# Control.net
KiCad netlist of a schematic drawn in Altium Designer
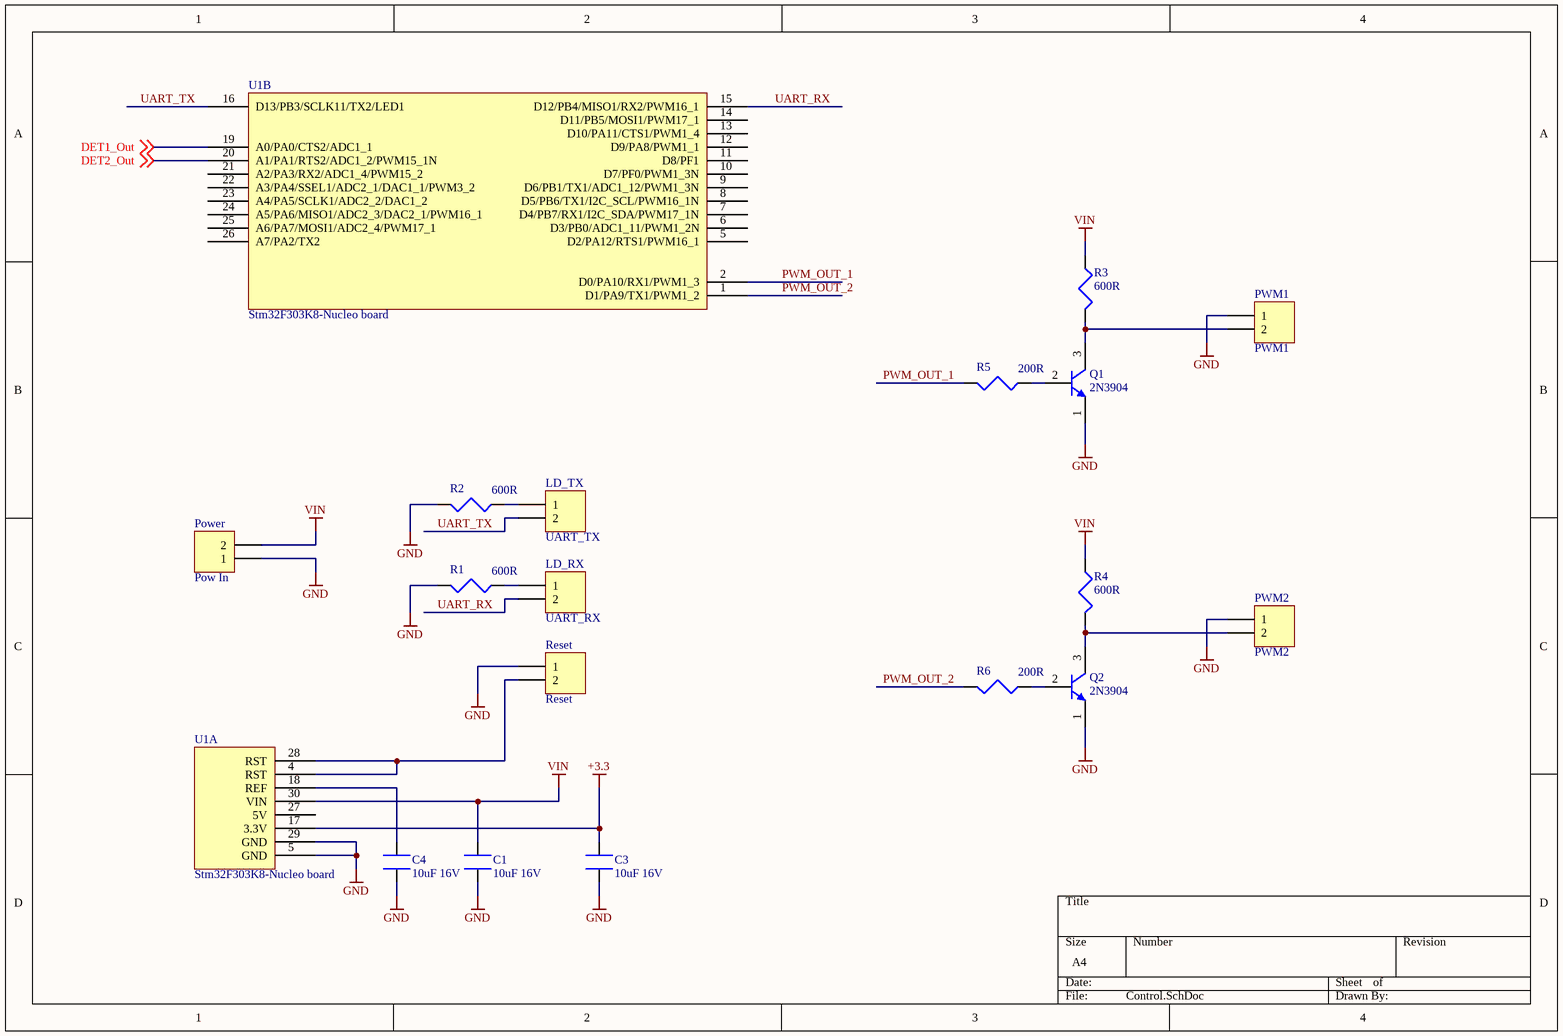
[diagram p0: Control.SchDoc]

(export (version "E")
  (design (tool "Eeschema 10.0.6"))
  (components
    (comp (ref "C1") (value "10uF 16V") (footprint "0805_C") (libsource (lib "Schlib1") (part "Cap")))
    (comp (ref "C3") (value "10uF 16V") (footprint "0805_C") (libsource (lib "Schlib1") (part "Cap")))
    (comp (ref "C4") (value "10uF 16V") (footprint "0805_C") (libsource (lib "Schlib1") (part "Cap")))
    (comp (ref "LD_RX")
      (value "UART_RX")
      (footprint "HDR1X2")
      (description "Header, 2-Pin")
      (fields (field (name "PUBLISHER") "Altium Limited"))
      (libsource (lib "Miscellaneous Connectors") (part "Header 2"))
    )
    (comp (ref "LD_TX")
      (value "UART_TX")
      (footprint "HDR1X2")
      (description "Header, 2-Pin")
      (fields (field (name "PUBLISHER") "Altium Limited"))
      (libsource (lib "Miscellaneous Connectors") (part "Header 2"))
    )
    (comp (ref "Power")
      (value "Pow In")
      (footprint "HDR1X2")
      (description "Header, 2-Pin")
      (fields (field (name "PUBLISHER") "Altium Limited"))
      (libsource (lib "") (part "Header 2_1"))
    )
    (comp (ref "PWM1")
      (value "PWM1")
      (footprint "HDR1X2")
      (description "Header, 2-Pin")
      (fields (field (name "PUBLISHER") "Altium Limited"))
      (libsource (lib "Miscellaneous Connectors") (part "Header 2"))
    )
    (comp (ref "PWM2")
      (value "PWM2")
      (footprint "HDR1X2")
      (description "Header, 2-Pin")
      (fields (field (name "PUBLISHER") "Altium Limited"))
      (libsource (lib "Miscellaneous Connectors") (part "Header 2"))
    )
    (comp (ref "Q1")
      (value "2N3904")
      (footprint "ONSC-TO-92-3-29-11")
      (description "General Purpose Transistor, NPN Silicon, 200 mA, 60 V, -55 to 150 degC, 3-Pin TO-92, RoHS, Bulk")
      (fields (field (name "MANUFACTURER") "ONSemiconductor"))
      (libsource (lib "Altium Content Vault") (part "BJT-NPN-EBC-3"))
    )
    (comp (ref "Q2")
      (value "2N3904")
      (footprint "ONSC-TO-92-3-29-11")
      (description "General Purpose Transistor, NPN Silicon, 200 mA, 60 V, -55 to 150 degC, 3-Pin TO-92, RoHS, Bulk")
      (fields (field (name "MANUFACTURER") "ONSemiconductor"))
      (libsource (lib "Altium Content Vault") (part "BJT-NPN-EBC-3"))
    )
    (comp (ref "R1") (value "600R") (footprint "0805_R") (libsource (lib "Schlib1") (part "Res")))
    (comp (ref "R2") (value "600R") (footprint "0805_R") (libsource (lib "Schlib1") (part "Res")))
    (comp (ref "R3") (value "600R") (footprint "0805_R") (libsource (lib "Schlib1") (part "Res")))
    (comp (ref "R4") (value "600R") (footprint "0805_R") (libsource (lib "Schlib1") (part "Res")))
    (comp (ref "R5") (value "200R") (footprint "0805_R") (libsource (lib "Schlib1") (part "Res")))
    (comp (ref "R6") (value "200R") (footprint "0805_R") (libsource (lib "Schlib1") (part "Res")))
    (comp (ref "Reset")
      (value "Reset")
      (footprint "HDR1X2")
      (description "Header, 2-Pin")
      (fields (field (name "PUBLISHER") "Altium Limited"))
      (libsource (lib "Miscellaneous Connectors") (part "Header 2"))
    )
    (comp (ref "U1")
      (value "Stm32F303K8-Nucleo board")
      (footprint "F303-Nucleo")
      (libsource (lib "Schlib1") (part "F303-Nucleo"))
    )
  )
  (nets
    (net (code "1") (name "+3.3") (class "Default")
      (node (ref "C3") (pin "1") (pinfunction "1_1") (pintype "passive"))
      (node (ref "U1") (pin "17") (pinfunction "3.3V_17") (pintype "passive"))
    )
    (net (code "2") (name "/PWM_OUT_1") (class "Default")
      (node (ref "R5") (pin "1") (pinfunction "1_1") (pintype "passive"))
      (node (ref "U1") (pin "2") (pinfunction "D0/PA10/RX1/PWM1_3_2") (pintype "passive"))
    )
    (net (code "3") (name "/PWM_OUT_2") (class "Default")
      (node (ref "R6") (pin "1") (pinfunction "1_1") (pintype "passive"))
      (node (ref "U1") (pin "1") (pinfunction "D1/PA9/TX1/PWM1_2_1") (pintype "passive"))
    )
    (net (code "4") (name "/UART_RX") (class "Default")
      (node (ref "LD_RX") (pin "2") (pinfunction "2_2") (pintype "passive"))
      (node (ref "U1") (pin "15") (pinfunction "D12/PB4/MISO1/RX2/PWM16_1_15") (pintype "passive"))
    )
    (net (code "5") (name "/UART_TX") (class "Default")
      (node (ref "LD_TX") (pin "2") (pinfunction "2_2") (pintype "passive"))
      (node (ref "U1") (pin "16") (pinfunction "D13/PB3/SCLK11/TX2/LED1_16") (pintype "passive"))
    )
    (net (code "6") (name "DET1_Out") (class "Default")
      (node (ref "U1") (pin "19") (pinfunction "A0/PA0/CTS2/ADC1_1_19") (pintype "passive"))
    )
    (net (code "7") (name "DET2_Out") (class "Default")
      (node (ref "U1") (pin "20") (pinfunction "A1/PA1/RTS2/ADC1_2/PWM15_1N_20") (pintype "passive"))
    )
    (net (code "8") (name "GND") (class "Default")
      (node (ref "C1") (pin "2") (pinfunction "2_2") (pintype "passive"))
      (node (ref "C3") (pin "2") (pinfunction "2_2") (pintype "passive"))
      (node (ref "C4") (pin "2") (pinfunction "2_2") (pintype "passive"))
      (node (ref "PWM1") (pin "1") (pinfunction "1_1") (pintype "passive"))
      (node (ref "PWM2") (pin "1") (pinfunction "1_1") (pintype "passive"))
      (node (ref "Power") (pin "1") (pinfunction "1_1") (pintype "passive"))
      (node (ref "Q1") (pin "1") (pinfunction "E_1") (pintype "passive"))
      (node (ref "Q2") (pin "1") (pinfunction "E_1") (pintype "passive"))
      (node (ref "R1") (pin "1") (pinfunction "1_1") (pintype "passive"))
      (node (ref "R2") (pin "1") (pinfunction "1_1") (pintype "passive"))
      (node (ref "Reset") (pin "1") (pinfunction "1_1") (pintype "passive"))
      (node (ref "U1") (pin "29") (pinfunction "GND_29") (pintype "passive"))
      (node (ref "U1") (pin "5") (pinfunction "GND_5") (pintype "passive"))
    )
    (net (code "9") (name "Net-(LD_RX-Pad1)") (class "Default")
      (node (ref "LD_RX") (pin "1") (pinfunction "1_1") (pintype "passive"))
      (node (ref "R1") (pin "2") (pinfunction "2_2") (pintype "passive"))
    )
    (net (code "10") (name "Net-(LD_TX-Pad1)") (class "Default")
      (node (ref "LD_TX") (pin "1") (pinfunction "1_1") (pintype "passive"))
      (node (ref "R2") (pin "2") (pinfunction "2_2") (pintype "passive"))
    )
    (net (code "11") (name "Net-(Q1-B)") (class "Default")
      (node (ref "Q1") (pin "2") (pinfunction "B_2") (pintype "passive"))
      (node (ref "R5") (pin "2") (pinfunction "2_2") (pintype "passive"))
    )
    (net (code "12") (name "Net-(Q1-C)") (class "Default")
      (node (ref "PWM1") (pin "2") (pinfunction "2_2") (pintype "passive"))
      (node (ref "Q1") (pin "3") (pinfunction "C_3") (pintype "passive"))
      (node (ref "R3") (pin "1") (pinfunction "1_1") (pintype "passive"))
    )
    (net (code "13") (name "Net-(Q2-B)") (class "Default")
      (node (ref "Q2") (pin "2") (pinfunction "B_2") (pintype "passive"))
      (node (ref "R6") (pin "2") (pinfunction "2_2") (pintype "passive"))
    )
    (net (code "14") (name "Net-(Q2-C)") (class "Default")
      (node (ref "PWM2") (pin "2") (pinfunction "2_2") (pintype "passive"))
      (node (ref "Q2") (pin "3") (pinfunction "C_3") (pintype "passive"))
      (node (ref "R4") (pin "1") (pinfunction "1_1") (pintype "passive"))
    )
    (net (code "15") (name "Net-(Reset-Pad2)") (class "Default")
      (node (ref "Reset") (pin "2") (pinfunction "2_2") (pintype "passive"))
      (node (ref "U1") (pin "28") (pinfunction "RST_28") (pintype "passive"))
      (node (ref "U1") (pin "4") (pinfunction "RST_4") (pintype "passive"))
    )
    (net (code "16") (name "Net-(U1A-REF)") (class "Default")
      (node (ref "C4") (pin "1") (pinfunction "1_1") (pintype "passive"))
      (node (ref "U1") (pin "18") (pinfunction "REF_18") (pintype "passive"))
    )
    (net (code "17") (name "VIN") (class "Default")
      (node (ref "C1") (pin "1") (pinfunction "1_1") (pintype "passive"))
      (node (ref "Power") (pin "2") (pinfunction "2_2") (pintype "passive"))
      (node (ref "R3") (pin "2") (pinfunction "2_2") (pintype "passive"))
      (node (ref "R4") (pin "2") (pinfunction "2_2") (pintype "passive"))
      (node (ref "U1") (pin "30") (pinfunction "VIN_30") (pintype "passive"))
    )
    (net (code "18") (name "unconnected-(U1A-5V-Pad27)") (class "Default")
      (node (ref "U1") (pin "27") (pinfunction "5V_27") (pintype "passive"))
    )
    (net (code "19") (name "unconnected-(U1B-A2{slash}PA3{slash}RX2{slash}ADC1_4{slash}PWM15_2-Pad21)") (class "Default")
      (node (ref "U1") (pin "21") (pinfunction "A2/PA3/RX2/ADC1_4/PWM15_2_21") (pintype "passive"))
    )
    (net (code "20") (name "unconnected-(U1B-A3{slash}PA4{slash}SSEL1{slash}ADC2_1{slash}DAC1_1{slash}PWM3_2-Pad22)") (class "Default")
      (node (ref "U1") (pin "22") (pinfunction "A3/PA4/SSEL1/ADC2_1/DAC1_1/PWM3_2_22") (pintype "passive"))
    )
    (net (code "21") (name "unconnected-(U1B-A4{slash}PA5{slash}SCLK1{slash}ADC2_2{slash}DAC1_2-Pad23)") (class "Default")
      (node (ref "U1") (pin "23") (pinfunction "A4/PA5/SCLK1/ADC2_2/DAC1_2_23") (pintype "passive"))
    )
    (net (code "22") (name "unconnected-(U1B-A5{slash}PA6{slash}MISO1{slash}ADC2_3{slash}DAC2_1{slash}PWM16_1-Pad24)") (class "Default")
      (node (ref "U1") (pin "24") (pinfunction "A5/PA6/MISO1/ADC2_3/DAC2_1/PWM16_1_24") (pintype "passive"))
    )
    (net (code "23") (name "unconnected-(U1B-A6{slash}PA7{slash}MOSI1{slash}ADC2_4{slash}PWM17_1-Pad25)") (class "Default")
      (node (ref "U1") (pin "25") (pinfunction "A6/PA7/MOSI1/ADC2_4/PWM17_1_25") (pintype "passive"))
    )
    (net (code "24") (name "unconnected-(U1B-A7{slash}PA2{slash}TX2-Pad26)") (class "Default")
      (node (ref "U1") (pin "26") (pinfunction "A7/PA2/TX2_26") (pintype "passive"))
    )
    (net (code "25") (name "unconnected-(U1B-D2{slash}PA12{slash}RTS1{slash}PWM16_1-Pad5)") (class "Default")
      (node (ref "U1") (pin "5") (pinfunction "D2/PA12/RTS1/PWM16_1_5") (pintype "passive"))
    )
    (net (code "26") (name "unconnected-(U1B-D3{slash}PB0{slash}ADC1_11{slash}PWM1_2N-Pad6)") (class "Default")
      (node (ref "U1") (pin "6") (pinfunction "D3/PB0/ADC1_11/PWM1_2N_6") (pintype "passive"))
    )
    (net (code "27") (name "unconnected-(U1B-D4{slash}PB7{slash}RX1{slash}I2C_SDA{slash}PWM17_1N-Pad7)") (class "Default")
      (node (ref "U1") (pin "7") (pinfunction "D4/PB7/RX1/I2C_SDA/PWM17_1N_7") (pintype "passive"))
    )
    (net (code "28") (name "unconnected-(U1B-D5{slash}PB6{slash}TX1{slash}I2C_SCL{slash}PWM16_1N-Pad8)") (class "Default")
      (node (ref "U1") (pin "8") (pinfunction "D5/PB6/TX1/I2C_SCL/PWM16_1N_8") (pintype "passive"))
    )
    (net (code "29") (name "unconnected-(U1B-D6{slash}PB1{slash}TX1{slash}ADC1_12{slash}PWM1_3N-Pad9)") (class "Default")
      (node (ref "U1") (pin "9") (pinfunction "D6/PB1/TX1/ADC1_12/PWM1_3N_9") (pintype "passive"))
    )
    (net (code "30") (name "unconnected-(U1B-D7{slash}PF0{slash}PWM1_3N-Pad10)") (class "Default")
      (node (ref "U1") (pin "10") (pinfunction "D7/PF0/PWM1_3N_10") (pintype "passive"))
    )
    (net (code "31") (name "unconnected-(U1B-D8{slash}PF1-Pad11)") (class "Default")
      (node (ref "U1") (pin "11") (pinfunction "D8/PF1_11") (pintype "passive"))
    )
    (net (code "32") (name "unconnected-(U1B-D9{slash}PA8{slash}PWM1_1-Pad12)") (class "Default")
      (node (ref "U1") (pin "12") (pinfunction "D9/PA8/PWM1_1_12") (pintype "passive"))
    )
    (net (code "33") (name "unconnected-(U1B-D10{slash}PA11{slash}CTS1{slash}PWM1_4-Pad13)") (class "Default")
      (node (ref "U1") (pin "13") (pinfunction "D10/PA11/CTS1/PWM1_4_13") (pintype "passive"))
    )
    (net (code "34") (name "unconnected-(U1B-D11{slash}PB5{slash}MOSI1{slash}PWM17_1-Pad14)") (class "Default")
      (node (ref "U1") (pin "14") (pinfunction "D11/PB5/MOSI1/PWM17_1_14") (pintype "passive"))
    )
  )
)
